# Power.net
KiCad netlist of a schematic drawn in Altium Designer
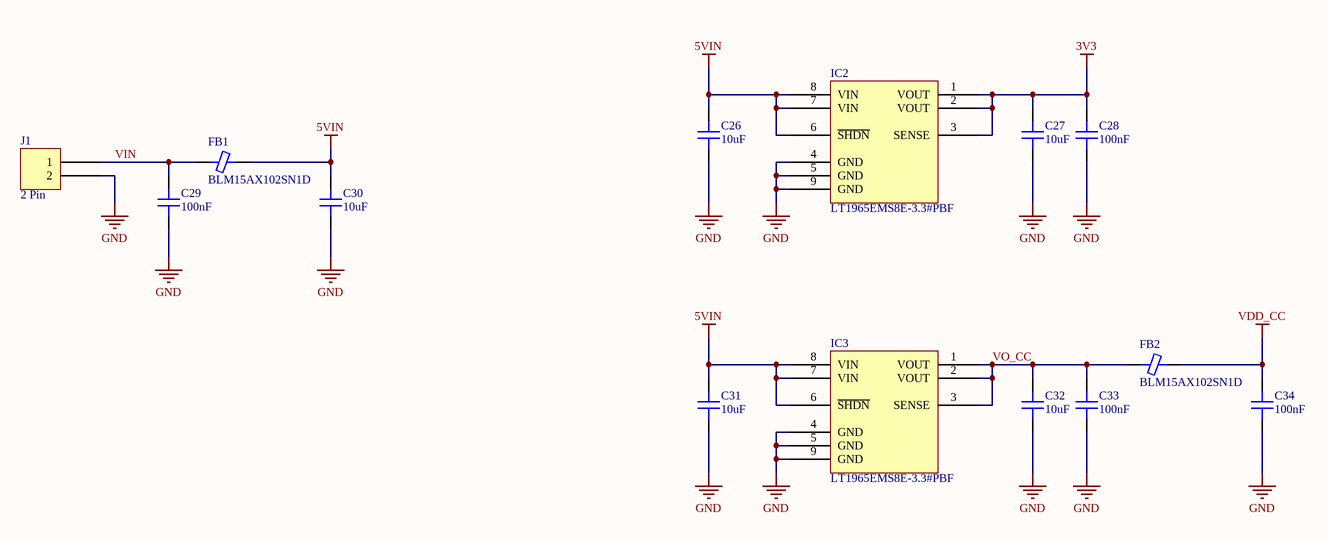
[diagram p0: Power.SchDoc]

(export (version "E")
  (design (tool "Eeschema 10.0.6"))
  (components
    (comp (ref "C26")
      (value "10uF")
      (footprint "CAP 0805/2012")
      (description "Cap Ceramic 10uF 10V X5R 10% SMD 0805 85C Embossed T/R")
      (fields (field (name "TOLERANCE") "10%") (field (name "VOLTAGE") "10V"))
      (libsource (lib "SCH - PASSIVES - CAPACITOR") (part "Capacitor"))
    )
    (comp (ref "C27")
      (value "10uF")
      (footprint "CAP 0805/2012")
      (description "Cap Ceramic 10uF 10V X5R 10% SMD 0805 85C Embossed T/R")
      (fields (field (name "TOLERANCE") "10%") (field (name "VOLTAGE") "10V"))
      (libsource (lib "SCH - PASSIVES - CAPACITOR") (part "Capacitor"))
    )
    (comp (ref "C28")
      (value "100nF")
      (footprint "CAP 0402/1005")
      (description "Cap Ceramic 0.1uF 10V X5R 20% Pad SMD 0402 85C T/R")
      (fields (field (name "TOLERANCE") "20%"))
      (libsource (lib "SCH - PASSIVES - CAPACITOR") (part "Capacitor"))
    )
    (comp (ref "C29")
      (value "100nF")
      (footprint "CAP 0402/1005")
      (description "Cap Ceramic 0.1uF 10V X5R 20% Pad SMD 0402 85C T/R")
      (fields (field (name "TOLERANCE") "20%"))
      (libsource (lib "SCH - PASSIVES - CAPACITOR") (part "Capacitor"))
    )
    (comp (ref "C30")
      (value "10uF")
      (footprint "CAP 0805/2012")
      (description "Cap Ceramic 10uF 10V X5R 10% SMD 0805 85C Embossed T/R")
      (fields (field (name "TOLERANCE") "10%") (field (name "VOLTAGE") "10V"))
      (libsource (lib "SCH - PASSIVES - CAPACITOR") (part "Capacitor"))
    )
    (comp (ref "C31")
      (value "10uF")
      (footprint "CAP 0805/2012")
      (description "Cap Ceramic 10uF 10V X5R 10% SMD 0805 85C Embossed T/R")
      (fields (field (name "TOLERANCE") "10%") (field (name "VOLTAGE") "10V"))
      (libsource (lib "SCH - PASSIVES - CAPACITOR") (part "Capacitor"))
    )
    (comp (ref "C32")
      (value "10uF")
      (footprint "CAP 0805/2012")
      (description "Cap Ceramic 10uF 10V X5R 10% SMD 0805 85C Embossed T/R")
      (fields (field (name "TOLERANCE") "10%") (field (name "VOLTAGE") "10V"))
      (libsource (lib "SCH - PASSIVES - CAPACITOR") (part "Capacitor"))
    )
    (comp (ref "C33")
      (value "100nF")
      (footprint "CAP 0402/1005")
      (description "Cap Ceramic 0.1uF 10V X5R 20% Pad SMD 0402 85C T/R")
      (fields (field (name "TOLERANCE") "20%"))
      (libsource (lib "SCH - PASSIVES - CAPACITOR") (part "Capacitor"))
    )
    (comp (ref "C34")
      (value "100nF")
      (footprint "CAP 0402/1005")
      (description "Cap Ceramic 0.1uF 10V X5R 20% Pad SMD 0402 85C T/R")
      (fields (field (name "TOLERANCE") "20%"))
      (libsource (lib "SCH - PASSIVES - CAPACITOR") (part "Capacitor"))
    )
    (comp (ref "FB1")
      (value "BLM15AX102SN1D")
      (footprint "FER 0402/1005")
      (description "Ferrite Beads Multi-Layer 1KOhm 25% 100MHz 350mA 490mOhm DCR 0402 T/R")
      (fields (field (name "TOLERANCE") "25%"))
      (libsource (lib "SCH - PASSIVES - FERRITE CHIP") (part "Ferrite Chip"))
    )
    (comp (ref "FB2")
      (value "BLM15AX102SN1D")
      (footprint "FER 0402/1005")
      (description "Ferrite Beads Multi-Layer 1KOhm 25% 100MHz 350mA 490mOhm DCR 0402 T/R")
      (fields (field (name "TOLERANCE") "25%"))
      (libsource (lib "SCH - PASSIVES - FERRITE CHIP") (part "Ferrite Chip"))
    )
    (comp (ref "IC2")
      (value "LT1965EMS8E-3.3#PBF")
      (footprint "LT MSOP-8 MS8E 3x3MM")
      (description "IC REG LINEAR 3.3V 1.1A 8MSOP")
      (libsource (lib "SCH - POWER - LINEAR VREG - LT LT1965 DD_MS8E") (part "LT LT1965 DD/MS8E"))
    )
    (comp (ref "IC3")
      (value "LT1965EMS8E-3.3#PBF")
      (footprint "LT MSOP-8 MS8E 3x3MM")
      (description "IC REG LINEAR 3.3V 1.1A 8MSOP")
      (libsource (lib "SCH - POWER - LINEAR VREG - LT LT1965 DD_MS8E") (part "LT LT1965 DD/MS8E"))
    )
    (comp (ref "J1")
      (value "2 Pin")
      (footprint "FCI 06-381-2PIN")
      (description "TERM BLOCK HDR 2POS 90DEG 3.81MM")
      (libsource (lib "SCH - CONNECTORS - 2 PIN") (part "2 Pin"))
    )
  )
  (nets
    (net (code "1") (name "/VIN") (class "Default")
      (node (ref "C29") (pin "2") (pinfunction "2_2") (pintype "passive"))
      (node (ref "FB1") (pin "2") (pinfunction "2_2") (pintype "passive"))
      (node (ref "J1") (pin "1") (pinfunction "1_1") (pintype "passive"))
    )
    (net (code "2") (name "/VO_CC") (class "Default")
      (node (ref "C32") (pin "2") (pinfunction "2_2") (pintype "passive"))
      (node (ref "C33") (pin "2") (pinfunction "2_2") (pintype "passive"))
      (node (ref "FB2") (pin "2") (pinfunction "2_2") (pintype "passive"))
      (node (ref "IC3") (pin "1") (pinfunction "VOUT_1") (pintype "passive"))
      (node (ref "IC3") (pin "2") (pinfunction "VOUT_2") (pintype "passive"))
      (node (ref "IC3") (pin "3") (pinfunction "SENSE_3") (pintype "passive"))
    )
    (net (code "3") (name "3V3") (class "Default")
      (node (ref "C27") (pin "2") (pinfunction "2_2") (pintype "passive"))
      (node (ref "C28") (pin "2") (pinfunction "2_2") (pintype "passive"))
      (node (ref "IC2") (pin "1") (pinfunction "VOUT_1") (pintype "passive"))
      (node (ref "IC2") (pin "2") (pinfunction "VOUT_2") (pintype "passive"))
      (node (ref "IC2") (pin "3") (pinfunction "SENSE_3") (pintype "passive"))
    )
    (net (code "4") (name "5VIN") (class "Default")
      (node (ref "C26") (pin "2") (pinfunction "2_2") (pintype "passive"))
      (node (ref "C30") (pin "2") (pinfunction "2_2") (pintype "passive"))
      (node (ref "C31") (pin "2") (pinfunction "2_2") (pintype "passive"))
      (node (ref "FB1") (pin "1") (pinfunction "1_1") (pintype "passive"))
      (node (ref "IC2") (pin "6") (pinfunction "~{SHDN}_6") (pintype "passive"))
      (node (ref "IC2") (pin "7") (pinfunction "VIN_7") (pintype "passive"))
      (node (ref "IC2") (pin "8") (pinfunction "VIN_8") (pintype "passive"))
      (node (ref "IC3") (pin "6") (pinfunction "~{SHDN}_6") (pintype "passive"))
      (node (ref "IC3") (pin "7") (pinfunction "VIN_7") (pintype "passive"))
      (node (ref "IC3") (pin "8") (pinfunction "VIN_8") (pintype "passive"))
    )
    (net (code "5") (name "GND") (class "Default")
      (node (ref "C26") (pin "1") (pinfunction "1_1") (pintype "passive"))
      (node (ref "C27") (pin "1") (pinfunction "1_1") (pintype "passive"))
      (node (ref "C28") (pin "1") (pinfunction "1_1") (pintype "passive"))
      (node (ref "C29") (pin "1") (pinfunction "1_1") (pintype "passive"))
      (node (ref "C30") (pin "1") (pinfunction "1_1") (pintype "passive"))
      (node (ref "C31") (pin "1") (pinfunction "1_1") (pintype "passive"))
      (node (ref "C32") (pin "1") (pinfunction "1_1") (pintype "passive"))
      (node (ref "C33") (pin "1") (pinfunction "1_1") (pintype "passive"))
      (node (ref "C34") (pin "1") (pinfunction "1_1") (pintype "passive"))
      (node (ref "IC2") (pin "4") (pinfunction "GND_4") (pintype "passive"))
      (node (ref "IC2") (pin "5") (pinfunction "GND_5") (pintype "passive"))
      (node (ref "IC2") (pin "9") (pinfunction "GND_9") (pintype "passive"))
      (node (ref "IC3") (pin "4") (pinfunction "GND_4") (pintype "passive"))
      (node (ref "IC3") (pin "5") (pinfunction "GND_5") (pintype "passive"))
      (node (ref "IC3") (pin "9") (pinfunction "GND_9") (pintype "passive"))
      (node (ref "J1") (pin "2") (pinfunction "2_2") (pintype "passive"))
    )
    (net (code "6") (name "VDD_CC") (class "Default")
      (node (ref "C34") (pin "2") (pinfunction "2_2") (pintype "passive"))
      (node (ref "FB2") (pin "1") (pinfunction "1_1") (pintype "passive"))
    )
  )
)
